# untitled.net
KiCad netlist of a schematic drawn in EAGLE
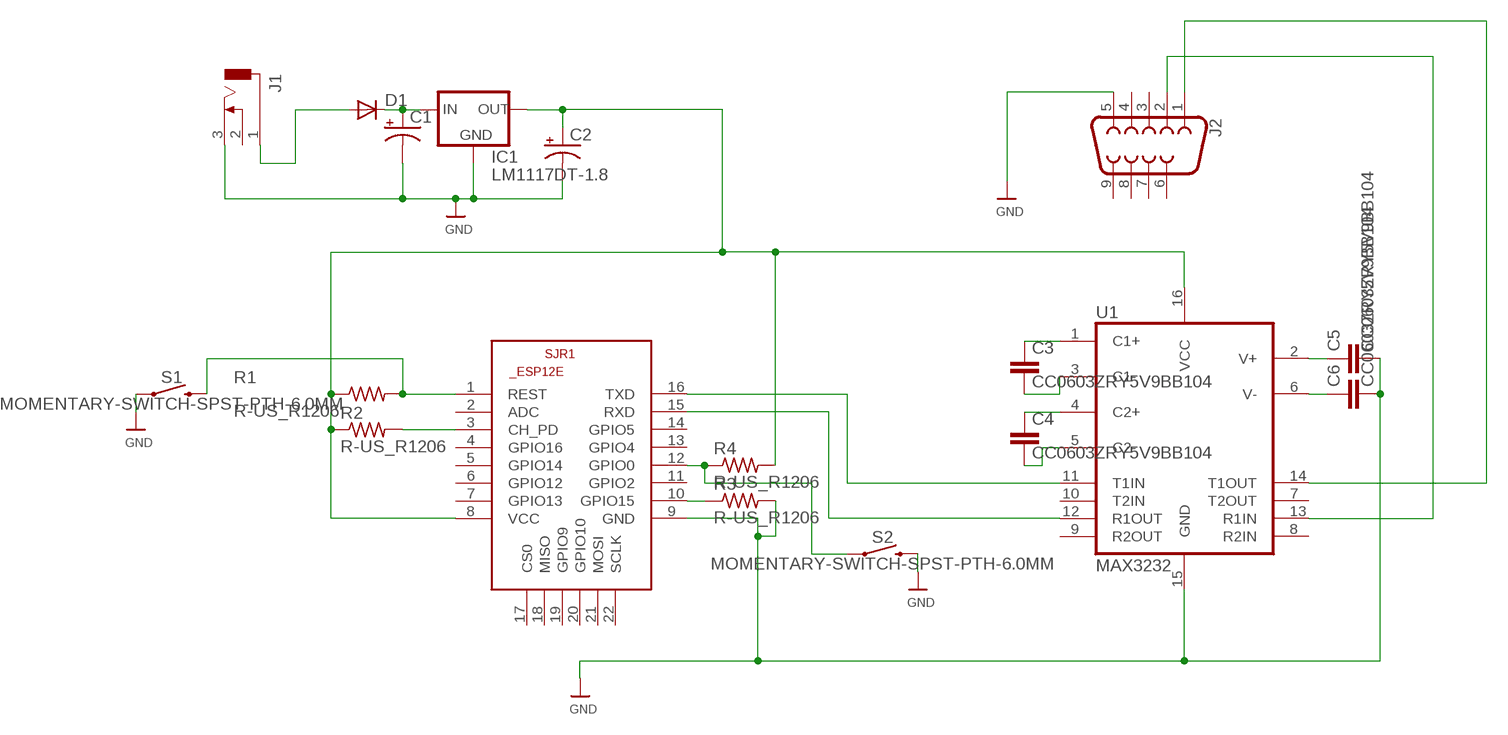
[diagram p0: schematic, sheet 1]

(export (version "E")
  (design (tool "Eeschema 10.0.6"))
  (components
    (comp (ref "C1")
      (value "CPOL-US175TMP-0810")
      (footprint "eagle-import:175TMP-0810")
      (libsource (lib "eagle-import") (part "CPOL-US175TMP-0810"))
    )
    (comp (ref "C2")
      (value "CPOL-US175TMP-0810")
      (footprint "eagle-import:175TMP-0810")
      (libsource (lib "eagle-import") (part "CPOL-US175TMP-0810"))
    )
    (comp (ref "C3")
      (value "CC0603ZRY5V9BB104")
      (footprint "eagle-import:CC0603ZRY5V9BB104")
      (fields (field (name "MANUFACTURER") "Yageo"))
      (libsource (lib "eagle-import") (part "CC0603ZRY5V9BB104"))
    )
    (comp (ref "C4")
      (value "CC0603ZRY5V9BB104")
      (footprint "eagle-import:CC0603ZRY5V9BB104")
      (fields (field (name "MANUFACTURER") "Yageo"))
      (libsource (lib "eagle-import") (part "CC0603ZRY5V9BB104"))
    )
    (comp (ref "C5")
      (value "CC0603ZRY5V9BB104")
      (footprint "eagle-import:CC0603ZRY5V9BB104")
      (fields (field (name "MANUFACTURER") "Yageo"))
      (libsource (lib "eagle-import") (part "CC0603ZRY5V9BB104"))
    )
    (comp (ref "C6")
      (value "CC0603ZRY5V9BB104")
      (footprint "eagle-import:CC0603ZRY5V9BB104")
      (fields (field (name "MANUFACTURER") "Yageo"))
      (libsource (lib "eagle-import") (part "CC0603ZRY5V9BB104"))
    )
    (comp (ref "D1")
      (value "DIODESMA")
      (footprint "eagle-import:SMADIODE")
      (libsource (lib "eagle-import") (part "DIODESMA"))
    )
    (comp (ref "IC1")
      (value "LM1117DT-1.8")
      (footprint "eagle-import:TO252")
      (fields (field (name "MF") "Texas Instruments"))
      (libsource (lib "eagle-import") (part "LM1117?-DT1.8"))
    )
    (comp (ref "J1")
      (value "DCJ0303")
      (footprint "eagle-import:DCJ0303")
      (libsource (lib "eagle-import") (part "DCJ0303"))
    )
    (comp (ref "J2")
      (value "DB9MALE")
      (footprint "eagle-import:DB9_MALE")
      (libsource (lib "eagle-import") (part "DB9MALE"))
    )
    (comp (ref "R1")
      (value "R-US_R1206")
      (footprint "eagle-import:R1206")
      (libsource (lib "eagle-import") (part "R-US_R1206"))
    )
    (comp (ref "R2")
      (value "R-US_R1206")
      (footprint "eagle-import:R1206")
      (libsource (lib "eagle-import") (part "R-US_R1206"))
    )
    (comp (ref "R3")
      (value "R-US_R1206")
      (footprint "eagle-import:R1206")
      (libsource (lib "eagle-import") (part "R-US_R1206"))
    )
    (comp (ref "R4")
      (value "R-US_R1206")
      (footprint "eagle-import:R1206")
      (libsource (lib "eagle-import") (part "R-US_R1206"))
    )
    (comp (ref "S1")
      (value "MOMENTARY-SWITCH-SPST-PTH-6.0MM")
      (footprint "eagle-import:TACTILE_SWITCH_PTH_6.0MM")
      (libsource (lib "eagle-import") (part "MOMENTARY-SWITCH-SPST-PTH-6.0MM"))
    )
    (comp (ref "S2")
      (value "MOMENTARY-SWITCH-SPST-PTH-6.0MM")
      (footprint "eagle-import:TACTILE_SWITCH_PTH_6.0MM")
      (libsource (lib "eagle-import") (part "MOMENTARY-SWITCH-SPST-PTH-6.0MM"))
    )
    (comp (ref "SJR1")
      (value "ESP8266-12EESP12E")
      (footprint "eagle-import:ESP8266-ESP12E")
      (libsource (lib "eagle-import") (part "ESP8266-12EESP12E"))
    )
    (comp (ref "U1")
      (value "MAX3232")
      (footprint "eagle-import:SO16")
      (libsource (lib "eagle-import") (part "MAX2323SOIC16"))
    )
  )
  (nets
    (net (code "1") (name "GND") (class "Default")
      (node (ref "C1") (pin "-") (pinfunction "-_-") (pintype "passive"))
      (node (ref "C2") (pin "-") (pinfunction "-_-") (pintype "passive"))
      (node (ref "C5") (pin "2") (pinfunction "2_2") (pintype "passive"))
      (node (ref "C6") (pin "2") (pinfunction "2_2") (pintype "passive"))
      (node (ref "IC1") (pin "1") (pinfunction "GND_1") (pintype "input"))
      (node (ref "J1") (pin "3") (pinfunction "3_3") (pintype "passive"))
      (node (ref "J2") (pin "5") (pinfunction "5_5") (pintype "passive"))
      (node (ref "R3") (pin "2") (pinfunction "2_2") (pintype "passive"))
      (node (ref "S1") (pin "1") (pinfunction "1_1") (pintype "passive"))
      (node (ref "S2") (pin "3") (pinfunction "2_3") (pintype "passive"))
      (node (ref "SJR1") (pin "9") (pinfunction "GND_9") (pintype "bidirectional"))
      (node (ref "U1") (pin "15") (pinfunction "GND_15") (pintype "bidirectional"))
    )
    (net (code "2") (name "Net-(D1-PadA)") (class "Default")
      (node (ref "D1") (pin "A") (pinfunction "A_A") (pintype "passive"))
      (node (ref "J1") (pin "1") (pinfunction "1_1") (pintype "passive"))
    )
    (net (code "3") (name "Net-(IC1-IN)") (class "Default")
      (node (ref "C1") (pin "+") (pinfunction "+_+") (pintype "passive"))
      (node (ref "D1") (pin "C") (pinfunction "C_C") (pintype "passive"))
      (node (ref "IC1") (pin "2") (pinfunction "IN_2") (pintype "input"))
    )
    (net (code "4") (name "Net-(IC1-OUT)") (class "Default")
      (node (ref "C2") (pin "+") (pinfunction "+_+") (pintype "passive"))
      (node (ref "IC1") (pin "3") (pinfunction "OUT_3") (pintype "passive"))
      (node (ref "R1") (pin "1") (pinfunction "1_1") (pintype "passive"))
      (node (ref "R2") (pin "1") (pinfunction "1_1") (pintype "passive"))
      (node (ref "R4") (pin "2") (pinfunction "2_2") (pintype "passive"))
      (node (ref "SJR1") (pin "8") (pinfunction "VCC_8") (pintype "bidirectional"))
      (node (ref "U1") (pin "16") (pinfunction "VCC_16") (pintype "bidirectional"))
    )
    (net (code "5") (name "Net-(S1-2)") (class "Default")
      (node (ref "R1") (pin "2") (pinfunction "2_2") (pintype "passive"))
      (node (ref "S1") (pin "3") (pinfunction "2_3") (pintype "passive"))
      (node (ref "SJR1") (pin "1") (pinfunction "REST_1") (pintype "bidirectional"))
    )
    (net (code "6") (name "Net-(SJR1-CH_PD)") (class "Default")
      (node (ref "R2") (pin "2") (pinfunction "2_2") (pintype "passive"))
      (node (ref "SJR1") (pin "3") (pinfunction "CH_PD_3") (pintype "bidirectional"))
    )
    (net (code "7") (name "Net-(SJR1-GPIO0)") (class "Default")
      (node (ref "R4") (pin "1") (pinfunction "1_1") (pintype "passive"))
      (node (ref "S2") (pin "1") (pinfunction "1_1") (pintype "passive"))
      (node (ref "SJR1") (pin "12") (pinfunction "GPIO0_12") (pintype "bidirectional"))
    )
    (net (code "8") (name "Net-(SJR1-GPIO15)") (class "Default")
      (node (ref "R3") (pin "1") (pinfunction "1_1") (pintype "passive"))
      (node (ref "SJR1") (pin "10") (pinfunction "GPIO15_10") (pintype "bidirectional"))
    )
    (net (code "9") (name "Net-(SJR1-RXD)") (class "Default")
      (node (ref "SJR1") (pin "15") (pinfunction "RXD_15") (pintype "bidirectional"))
      (node (ref "U1") (pin "12") (pinfunction "R1OUT_12") (pintype "output"))
    )
    (net (code "10") (name "Net-(SJR1-TXD)") (class "Default")
      (node (ref "SJR1") (pin "16") (pinfunction "TXD_16") (pintype "bidirectional"))
      (node (ref "U1") (pin "11") (pinfunction "T1IN_11") (pintype "input"))
    )
    (net (code "11") (name "Net-(U1-C1+)") (class "Default")
      (node (ref "C3") (pin "1") (pinfunction "1_1") (pintype "passive"))
      (node (ref "U1") (pin "1") (pinfunction "C1+_1") (pintype "bidirectional"))
    )
    (net (code "12") (name "Net-(U1-C1-)") (class "Default")
      (node (ref "C3") (pin "2") (pinfunction "2_2") (pintype "passive"))
      (node (ref "U1") (pin "3") (pinfunction "C1-_3") (pintype "bidirectional"))
    )
    (net (code "13") (name "Net-(U1-C2+)") (class "Default")
      (node (ref "C4") (pin "1") (pinfunction "1_1") (pintype "passive"))
      (node (ref "U1") (pin "4") (pinfunction "C2+_4") (pintype "bidirectional"))
    )
    (net (code "14") (name "Net-(U1-C2-)") (class "Default")
      (node (ref "C4") (pin "2") (pinfunction "2_2") (pintype "passive"))
      (node (ref "U1") (pin "5") (pinfunction "C2-_5") (pintype "bidirectional"))
    )
    (net (code "15") (name "Net-(U1-R1IN)") (class "Default")
      (node (ref "J2") (pin "2") (pinfunction "2_2") (pintype "passive"))
      (node (ref "U1") (pin "13") (pinfunction "R1IN_13") (pintype "input"))
    )
    (net (code "16") (name "Net-(U1-T1OUT)") (class "Default")
      (node (ref "J2") (pin "1") (pinfunction "1_1") (pintype "passive"))
      (node (ref "U1") (pin "14") (pinfunction "T1OUT_14") (pintype "output"))
    )
    (net (code "17") (name "Net-(U1-V+)") (class "Default")
      (node (ref "C5") (pin "1") (pinfunction "1_1") (pintype "passive"))
      (node (ref "U1") (pin "2") (pinfunction "V+_2") (pintype "bidirectional"))
    )
    (net (code "18") (name "Net-(U1-V-)") (class "Default")
      (node (ref "C6") (pin "1") (pinfunction "1_1") (pintype "passive"))
      (node (ref "U1") (pin "6") (pinfunction "V-_6") (pintype "bidirectional"))
    )
    (net (code "19") (name "unconnected-(J1-Pad2)") (class "Default")
      (node (ref "J1") (pin "2") (pinfunction "2_2") (pintype "passive"))
    )
    (net (code "20") (name "unconnected-(J2-Pad3)") (class "Default")
      (node (ref "J2") (pin "3") (pinfunction "3_3") (pintype "passive"))
    )
    (net (code "21") (name "unconnected-(J2-Pad4)") (class "Default")
      (node (ref "J2") (pin "4") (pinfunction "4_4") (pintype "passive"))
    )
    (net (code "22") (name "unconnected-(J2-Pad6)") (class "Default")
      (node (ref "J2") (pin "6") (pinfunction "6_6") (pintype "passive"))
    )
    (net (code "23") (name "unconnected-(J2-Pad7)") (class "Default")
      (node (ref "J2") (pin "7") (pinfunction "7_7") (pintype "passive"))
    )
    (net (code "24") (name "unconnected-(J2-Pad8)") (class "Default")
      (node (ref "J2") (pin "8") (pinfunction "8_8") (pintype "passive"))
    )
    (net (code "25") (name "unconnected-(J2-Pad9)") (class "Default")
      (node (ref "J2") (pin "9") (pinfunction "9_9") (pintype "passive"))
    )
    (net (code "26") (name "unconnected-(SJR1-ADC-Pad2)") (class "Default")
      (node (ref "SJR1") (pin "2") (pinfunction "ADC_2") (pintype "bidirectional"))
    )
    (net (code "27") (name "unconnected-(SJR1-CS0-Pad17)") (class "Default")
      (node (ref "SJR1") (pin "17") (pinfunction "CS0_17") (pintype "bidirectional"))
    )
    (net (code "28") (name "unconnected-(SJR1-GPIO2-Pad11)") (class "Default")
      (node (ref "SJR1") (pin "11") (pinfunction "GPIO2_11") (pintype "bidirectional"))
    )
    (net (code "29") (name "unconnected-(SJR1-GPIO4-Pad13)") (class "Default")
      (node (ref "SJR1") (pin "13") (pinfunction "GPIO4_13") (pintype "bidirectional"))
    )
    (net (code "30") (name "unconnected-(SJR1-GPIO5-Pad14)") (class "Default")
      (node (ref "SJR1") (pin "14") (pinfunction "GPIO5_14") (pintype "bidirectional"))
    )
    (net (code "31") (name "unconnected-(SJR1-GPIO9-Pad19)") (class "Default")
      (node (ref "SJR1") (pin "19") (pinfunction "GPIO9_19") (pintype "bidirectional"))
    )
    (net (code "32") (name "unconnected-(SJR1-GPIO10-Pad20)") (class "Default")
      (node (ref "SJR1") (pin "20") (pinfunction "GPIO10_20") (pintype "bidirectional"))
    )
    (net (code "33") (name "unconnected-(SJR1-GPIO12-Pad6)") (class "Default")
      (node (ref "SJR1") (pin "6") (pinfunction "GPIO12_6") (pintype "bidirectional"))
    )
    (net (code "34") (name "unconnected-(SJR1-GPIO13-Pad7)") (class "Default")
      (node (ref "SJR1") (pin "7") (pinfunction "GPIO13_7") (pintype "bidirectional"))
    )
    (net (code "35") (name "unconnected-(SJR1-GPIO14-Pad5)") (class "Default")
      (node (ref "SJR1") (pin "5") (pinfunction "GPIO14_5") (pintype "bidirectional"))
    )
    (net (code "36") (name "unconnected-(SJR1-GPIO16-Pad4)") (class "Default")
      (node (ref "SJR1") (pin "4") (pinfunction "GPIO16_4") (pintype "bidirectional"))
    )
    (net (code "37") (name "unconnected-(SJR1-MISO-Pad18)") (class "Default")
      (node (ref "SJR1") (pin "18") (pinfunction "MISO_18") (pintype "bidirectional"))
    )
    (net (code "38") (name "unconnected-(SJR1-MOSI-Pad21)") (class "Default")
      (node (ref "SJR1") (pin "21") (pinfunction "MOSI_21") (pintype "bidirectional"))
    )
    (net (code "39") (name "unconnected-(SJR1-SCLK-Pad22)") (class "Default")
      (node (ref "SJR1") (pin "22") (pinfunction "SCLK_22") (pintype "bidirectional"))
    )
    (net (code "40") (name "unconnected-(U1-R2IN-Pad8)") (class "Default")
      (node (ref "U1") (pin "8") (pinfunction "R2IN_8") (pintype "input"))
    )
    (net (code "41") (name "unconnected-(U1-R2OUT-Pad9)") (class "Default")
      (node (ref "U1") (pin "9") (pinfunction "R2OUT_9") (pintype "output"))
    )
    (net (code "42") (name "unconnected-(U1-T2IN-Pad10)") (class "Default")
      (node (ref "U1") (pin "10") (pinfunction "T2IN_10") (pintype "input"))
    )
    (net (code "43") (name "unconnected-(U1-T2OUT-Pad7)") (class "Default")
      (node (ref "U1") (pin "7") (pinfunction "T2OUT_7") (pintype "output"))
    )
  )
)
